# TASK1.net
KiCad netlist of a schematic drawn in EasyEDA Pro
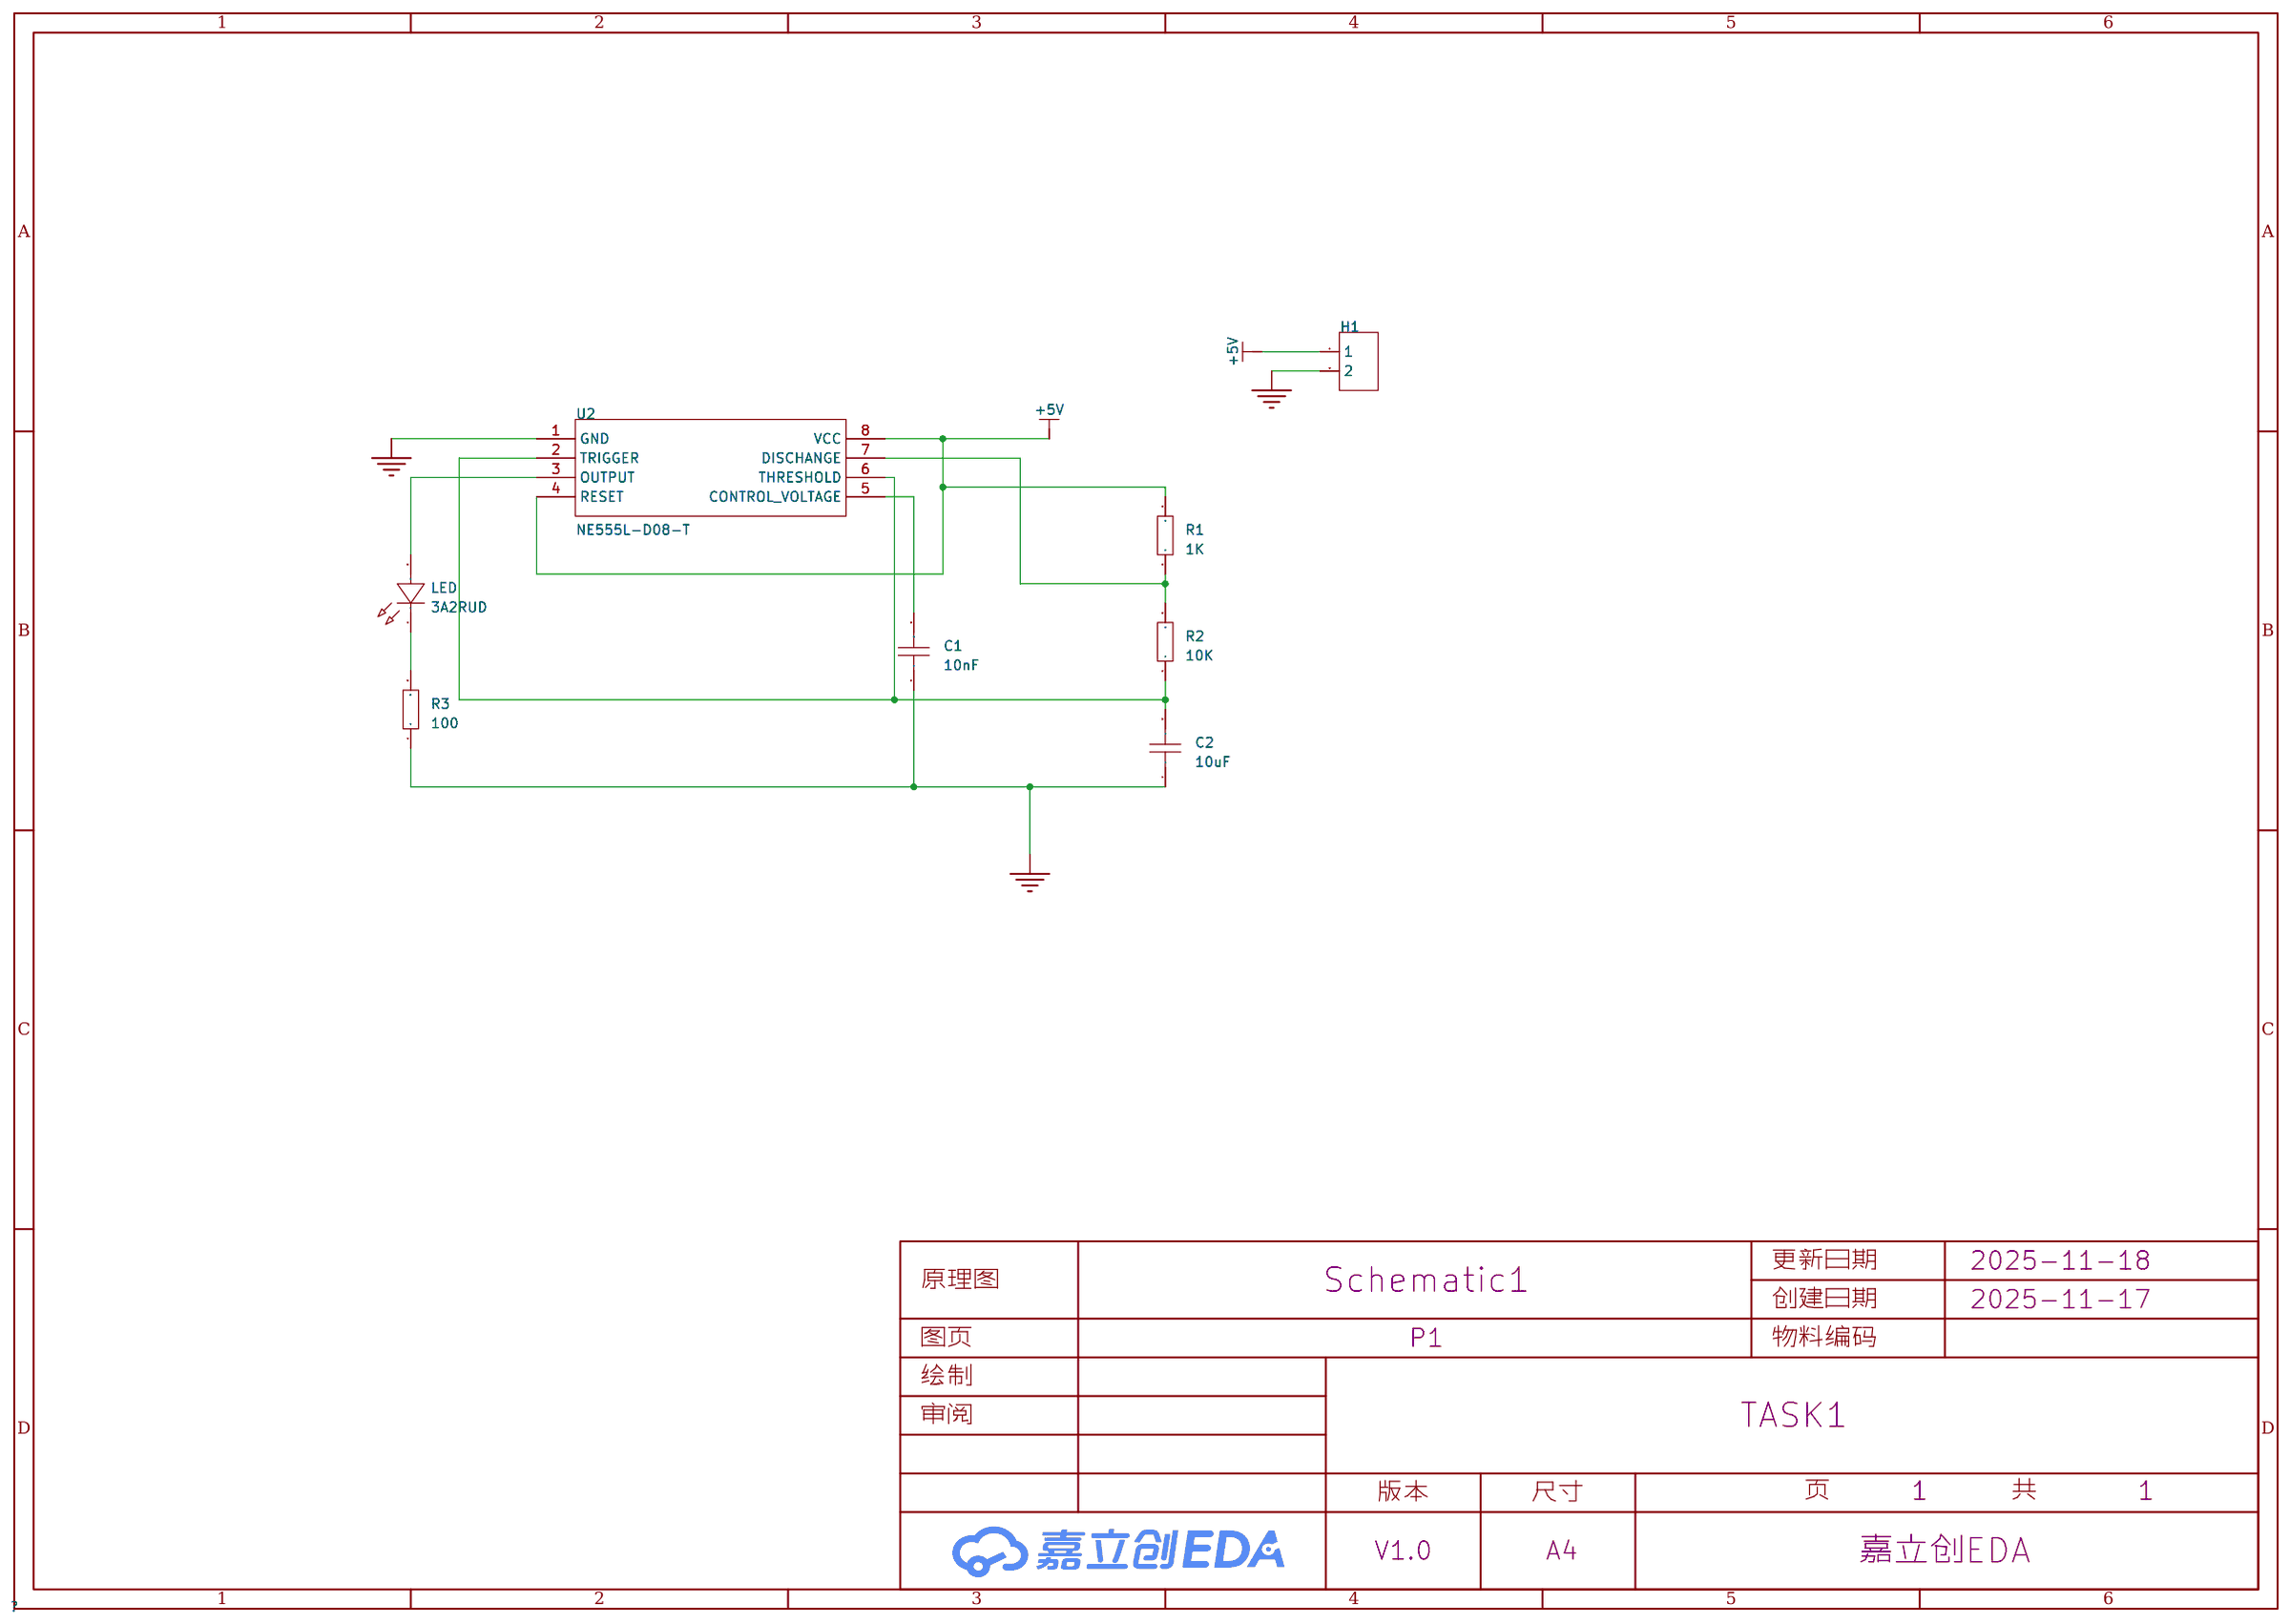
[diagram p0: schematic sheet]

(export (version "E")
  (design (tool "Eeschema 10.0.6"))
  (components
    (comp (ref "C1")
      (value "10nF")
      (footprint "easyedapro:C0603")
      (libsource (lib "easyedapro") (part "CapAcitance"))
    )
    (comp (ref "C2")
      (value "10uF")
      (footprint "easyedapro:C0603")
      (libsource (lib "easyedapro") (part "CapAcitance"))
    )
    (comp (ref "H1")
      (value "~")
      (footprint "easyedapro:HDR-TH_2P-P2.54-V-F")
      (libsource (lib "easyedapro") (part "Header-Female-2.54_1x2"))
    )
    (comp (ref "LED")
      (value "3A2RUD")
      (footprint "easyedapro:LED-TH_BD3.5-P2.28_3A2RUC")
      (fields (field (name "Manufacturer") "Guiguang light(桂光光电)"))
      (libsource (lib "easyedapro") (part "3A2RUD"))
    )
    (comp (ref "R1") (value "1K") (footprint "easyedapro:R0603") (libsource (lib "easyedapro") (part "电阻")))
    (comp (ref "R2") (value "10K") (footprint "easyedapro:R0603") (libsource (lib "easyedapro") (part "电阻")))
    (comp (ref "R3") (value "100") (footprint "easyedapro:R0603") (libsource (lib "easyedapro") (part "电阻")))
    (comp (ref "U2")
      (value "NE555L-D08-T")
      (footprint "easyedapro:DIP-8_L9.2-W6.4-P2.54-LS8.7-BL")
      (fields (field (name "Manufacturer") "UTC(友顺)"))
      (libsource (lib "easyedapro") (part "NE555L-D08-T"))
    )
  )
  (nets
    (net (code "1") (name "+5V") (class "Default")
      (node (ref "H1") (pin "1") (pinfunction "1_1") (pintype "input"))
      (node (ref "R1") (pin "2") (pinfunction "2_2") (pintype "input"))
      (node (ref "U2") (pin "4") (pinfunction "RESET_4") (pintype "input"))
      (node (ref "U2") (pin "8") (pinfunction "VCC_8") (pintype "input"))
    )
    (net (code "2") (name "GND") (class "Default")
      (node (ref "C1") (pin "1") (pinfunction "1_1") (pintype "input"))
      (node (ref "C2") (pin "1") (pinfunction "1_1") (pintype "input"))
      (node (ref "H1") (pin "2") (pinfunction "2_2") (pintype "input"))
      (node (ref "R3") (pin "1") (pinfunction "1_1") (pintype "input"))
      (node (ref "U2") (pin "1") (pinfunction "GND_1") (pintype "input"))
    )
    (net (code "3") (name "Net-(LED-A)") (class "Default")
      (node (ref "LED") (pin "2") (pinfunction "A_2") (pintype "unspecified"))
      (node (ref "U2") (pin "3") (pinfunction "OUTPUT_3") (pintype "input"))
    )
    (net (code "4") (name "Net-(LED-K)") (class "Default")
      (node (ref "LED") (pin "1") (pinfunction "K_1") (pintype "unspecified"))
      (node (ref "R3") (pin "2") (pinfunction "2_2") (pintype "input"))
    )
    (net (code "5") (name "Net-(U2-CONTROL_VOLTAGE)") (class "Default")
      (node (ref "C1") (pin "2") (pinfunction "2_2") (pintype "input"))
      (node (ref "U2") (pin "5") (pinfunction "CONTROL_VOLTAGE_5") (pintype "input"))
    )
    (net (code "6") (name "Net-(U2-DISCHANGE)") (class "Default")
      (node (ref "R1") (pin "1") (pinfunction "1_1") (pintype "input"))
      (node (ref "R2") (pin "2") (pinfunction "2_2") (pintype "input"))
      (node (ref "U2") (pin "7") (pinfunction "DISCHANGE_7") (pintype "input"))
    )
    (net (code "7") (name "Net-(U2-THRESHOLD)") (class "Default")
      (node (ref "C2") (pin "2") (pinfunction "2_2") (pintype "input"))
      (node (ref "R2") (pin "1") (pinfunction "1_1") (pintype "input"))
      (node (ref "U2") (pin "2") (pinfunction "TRIGGER_2") (pintype "input"))
      (node (ref "U2") (pin "6") (pinfunction "THRESHOLD_6") (pintype "input"))
    )
  )
)
